# TaaraESP-SHT21.net
KiCad netlist of a schematic drawn in EAGLE
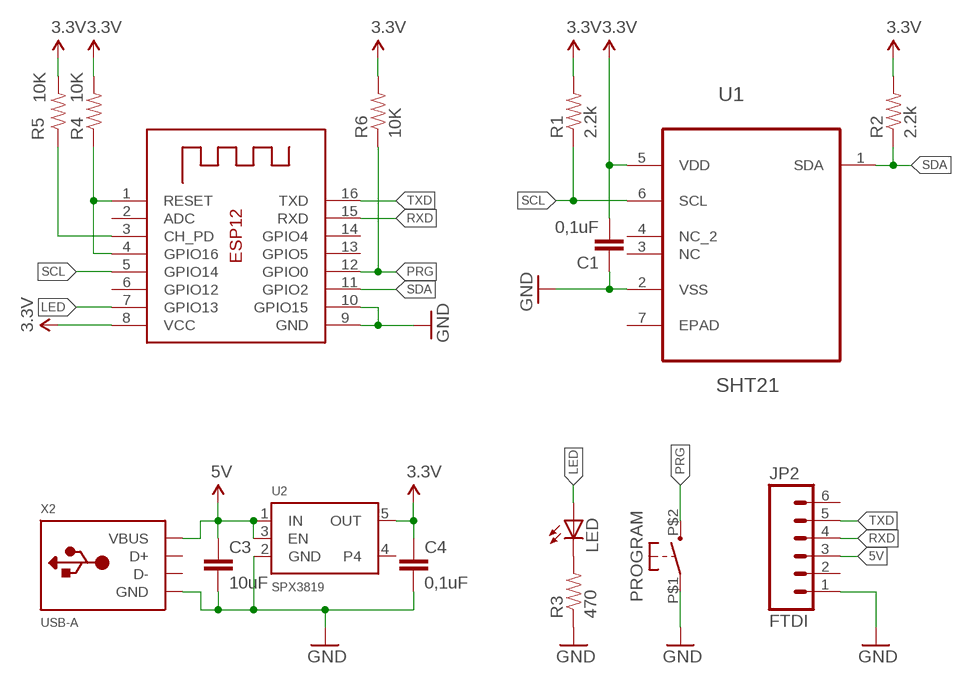
[diagram p0: schematic, sheet 1]

(export (version "E")
  (design (tool "Eeschema 10.0.6"))
  (components
    (comp (ref "C1")
      (value "0,1uF")
      (footprint "eagle-import:0603-CAP")
      (libsource (lib "eagle-import") (part "CAP0603-CAP"))
    )
    (comp (ref "C3")
      (value "10uF")
      (footprint "eagle-import:0603-CAP")
      (libsource (lib "eagle-import") (part "CAP0603-CAP"))
    )
    (comp (ref "C4")
      (value "0,1uF")
      (footprint "eagle-import:0603-CAP")
      (libsource (lib "eagle-import") (part "CAP0603-CAP"))
    )
    (comp (ref "JP2")
      (value "FTDI")
      (footprint "eagle-import:1X06-SIP_LOCK")
      (libsource (lib "eagle-import") (part "M06SIP_LOCK"))
    )
    (comp (ref "LED")
      (value "LEDCHIPLED_0603")
      (footprint "eagle-import:CHIPLED_0603")
      (libsource (lib "eagle-import") (part "LEDCHIPLED_0603"))
    )
    (comp (ref "PROGRAM")
      (value "OMRON_B3U-1000_TACT_SW")
      (footprint "eagle-import:BC3-1000")
      (libsource (lib "eagle-import") (part "OMRON_B3U-1000_TACT_SW"))
    )
    (comp (ref "R1")
      (value "2.2k")
      (footprint "eagle-import:0603-RES")
      (libsource (lib "eagle-import") (part "RESISTOR0603-RES"))
    )
    (comp (ref "R2")
      (value "2.2k")
      (footprint "eagle-import:0603-RES")
      (libsource (lib "eagle-import") (part "RESISTOR0603-RES"))
    )
    (comp (ref "R3")
      (value "470")
      (footprint "eagle-import:0603-RES")
      (libsource (lib "eagle-import") (part "RESISTOR0603-RES"))
    )
    (comp (ref "R4")
      (value "10K")
      (footprint "eagle-import:0603-RES")
      (libsource (lib "eagle-import") (part "RESISTOR0603-RES"))
    )
    (comp (ref "R5")
      (value "10K")
      (footprint "eagle-import:0603-RES")
      (libsource (lib "eagle-import") (part "RESISTOR0603-RES"))
    )
    (comp (ref "R6")
      (value "10K")
      (footprint "eagle-import:0603-RES")
      (libsource (lib "eagle-import") (part "RESISTOR0603-RES"))
    )
    (comp (ref "U1")
      (value "SHT21")
      (footprint "eagle-import:DFN300X300X110-7N")
      (libsource (lib "eagle-import") (part "SHT21"))
    )
    (comp (ref "U2")
      (value "SPX3819")
      (footprint "eagle-import:SOT23-5")
      (libsource (lib "eagle-import") (part "VREG_SOT23-5"))
    )
    (comp (ref "X1")
      (value "ESP-12")
      (footprint "eagle-import:ESP-12")
      (libsource (lib "eagle-import") (part "ESP-12"))
    )
    (comp (ref "X2")
      (value "USB-A")
      (footprint "eagle-import:MOLEX_480371000")
      (libsource (lib "eagle-import") (part "USB-A"))
    )
  )
  (nets
    (net (code "1") (name "3.3V") (class "Default")
      (node (ref "C1") (pin "2") (pinfunction "2_2") (pintype "passive"))
      (node (ref "C4") (pin "1") (pinfunction "1_1") (pintype "passive"))
      (node (ref "R1") (pin "2") (pinfunction "2_2") (pintype "passive"))
      (node (ref "R2") (pin "2") (pinfunction "2_2") (pintype "passive"))
      (node (ref "R4") (pin "2") (pinfunction "2_2") (pintype "passive"))
      (node (ref "R5") (pin "2") (pinfunction "2_2") (pintype "passive"))
      (node (ref "R6") (pin "2") (pinfunction "2_2") (pintype "passive"))
      (node (ref "U1") (pin "5") (pinfunction "VDD_5") (pintype "power_in"))
      (node (ref "U2") (pin "5") (pinfunction "OUT_5") (pintype "power_in"))
      (node (ref "X1") (pin "8") (pinfunction "VCC_8") (pintype "power_in"))
    )
    (net (code "2") (name "5V") (class "Default")
      (node (ref "C3") (pin "1") (pinfunction "1_1") (pintype "passive"))
      (node (ref "JP2") (pin "3") (pinfunction "3_3") (pintype "passive"))
      (node (ref "U2") (pin "1") (pinfunction "IN_1") (pintype "power_in"))
      (node (ref "U2") (pin "3") (pinfunction "EN_3") (pintype "input"))
      (node (ref "X2") (pin "1") (pinfunction "VBUS_1") (pintype "power_in"))
    )
    (net (code "3") (name "GND") (class "Default")
      (node (ref "C1") (pin "1") (pinfunction "1_1") (pintype "passive"))
      (node (ref "C3") (pin "2") (pinfunction "2_2") (pintype "passive"))
      (node (ref "C4") (pin "2") (pinfunction "2_2") (pintype "passive"))
      (node (ref "JP2") (pin "1") (pinfunction "1_1") (pintype "passive"))
      (node (ref "PROGRAM") (pin "P$1") (pinfunction "1_P$1") (pintype "passive"))
      (node (ref "R3") (pin "1") (pinfunction "1_1") (pintype "passive"))
      (node (ref "U1") (pin "2") (pinfunction "VSS_2") (pintype "power_in"))
      (node (ref "U2") (pin "2") (pinfunction "GND_2") (pintype "power_in"))
      (node (ref "X1") (pin "10") (pinfunction "GPIO15_10") (pintype "bidirectional"))
      (node (ref "X1") (pin "9") (pinfunction "GND_9") (pintype "power_in"))
      (node (ref "X2") (pin "4") (pinfunction "GND_4") (pintype "power_in"))
    )
    (net (code "4") (name "LED") (class "Default")
      (node (ref "LED") (pin "A") (pinfunction "A_A") (pintype "passive"))
      (node (ref "X1") (pin "7") (pinfunction "GPIO13_7") (pintype "bidirectional"))
    )
    (net (code "5") (name "Net-(LED-PadC)") (class "Default")
      (node (ref "LED") (pin "C") (pinfunction "C_C") (pintype "passive"))
      (node (ref "R3") (pin "2") (pinfunction "2_2") (pintype "passive"))
    )
    (net (code "6") (name "Net-(X1-CH_PD)") (class "Default")
      (node (ref "R5") (pin "1") (pinfunction "1_1") (pintype "passive"))
      (node (ref "X1") (pin "3") (pinfunction "CH_PD_3") (pintype "input"))
    )
    (net (code "7") (name "Net-(X1-GPIO16)") (class "Default")
      (node (ref "R4") (pin "1") (pinfunction "1_1") (pintype "passive"))
      (node (ref "X1") (pin "1") (pinfunction "RESET_1") (pintype "input"))
      (node (ref "X1") (pin "4") (pinfunction "GPIO16_4") (pintype "bidirectional"))
    )
    (net (code "8") (name "PRG") (class "Default")
      (node (ref "PROGRAM") (pin "P$2") (pinfunction "3_P$2") (pintype "passive"))
      (node (ref "R6") (pin "1") (pinfunction "1_1") (pintype "passive"))
      (node (ref "X1") (pin "12") (pinfunction "GPIO0_12") (pintype "bidirectional"))
    )
    (net (code "9") (name "RXD") (class "Default")
      (node (ref "JP2") (pin "4") (pinfunction "4_4") (pintype "passive"))
      (node (ref "X1") (pin "15") (pinfunction "RXD_15") (pintype "input"))
    )
    (net (code "10") (name "SCL") (class "Default")
      (node (ref "R1") (pin "1") (pinfunction "1_1") (pintype "passive"))
      (node (ref "U1") (pin "6") (pinfunction "SCL_6") (pintype "input"))
      (node (ref "X1") (pin "5") (pinfunction "GPIO14_5") (pintype "bidirectional"))
    )
    (net (code "11") (name "SDA") (class "Default")
      (node (ref "R2") (pin "1") (pinfunction "1_1") (pintype "passive"))
      (node (ref "U1") (pin "1") (pinfunction "SDA_1") (pintype "bidirectional"))
      (node (ref "X1") (pin "11") (pinfunction "GPIO2_11") (pintype "bidirectional"))
    )
    (net (code "12") (name "TXD") (class "Default")
      (node (ref "JP2") (pin "5") (pinfunction "5_5") (pintype "passive"))
      (node (ref "X1") (pin "16") (pinfunction "TXD_16") (pintype "output"))
    )
    (net (code "13") (name "unconnected-(JP2-Pad2)") (class "Default")
      (node (ref "JP2") (pin "2") (pinfunction "2_2") (pintype "passive"))
    )
    (net (code "14") (name "unconnected-(JP2-Pad6)") (class "Default")
      (node (ref "JP2") (pin "6") (pinfunction "6_6") (pintype "passive"))
    )
    (net (code "15") (name "unconnected-(U1-EPAD-Pad7)") (class "Default")
      (node (ref "U1") (pin "7") (pinfunction "EPAD_7") (pintype "passive"))
    )
    (net (code "16") (name "unconnected-(U1-NC-Pad3)") (class "Default")
      (node (ref "U1") (pin "3") (pinfunction "NC_3") (pintype "no_connect"))
    )
    (net (code "17") (name "unconnected-(U1-NC_2-Pad4)") (class "Default")
      (node (ref "U1") (pin "4") (pinfunction "NC_2_4") (pintype "no_connect"))
    )
    (net (code "18") (name "unconnected-(U2-P4-Pad4)") (class "Default")
      (node (ref "U2") (pin "4") (pinfunction "P4_4") (pintype "bidirectional"))
    )
    (net (code "19") (name "unconnected-(X1-ADC-Pad2)") (class "Default")
      (node (ref "X1") (pin "2") (pinfunction "ADC_2") (pintype "passive"))
    )
    (net (code "20") (name "unconnected-(X1-GPIO4-Pad14)") (class "Default")
      (node (ref "X1") (pin "14") (pinfunction "GPIO4_14") (pintype "bidirectional"))
    )
    (net (code "21") (name "unconnected-(X1-GPIO5-Pad13)") (class "Default")
      (node (ref "X1") (pin "13") (pinfunction "GPIO5_13") (pintype "bidirectional"))
    )
    (net (code "22") (name "unconnected-(X1-GPIO12-Pad6)") (class "Default")
      (node (ref "X1") (pin "6") (pinfunction "GPIO12_6") (pintype "bidirectional"))
    )
    (net (code "23") (name "unconnected-(X2-D+-Pad3)") (class "Default")
      (node (ref "X2") (pin "3") (pinfunction "D+_3") (pintype "bidirectional"))
    )
    (net (code "24") (name "unconnected-(X2-D--Pad2)") (class "Default")
      (node (ref "X2") (pin "2") (pinfunction "D-_2") (pintype "bidirectional"))
    )
  )
)
